# relay.net
KiCad netlist of a schematic drawn in Altium Designer
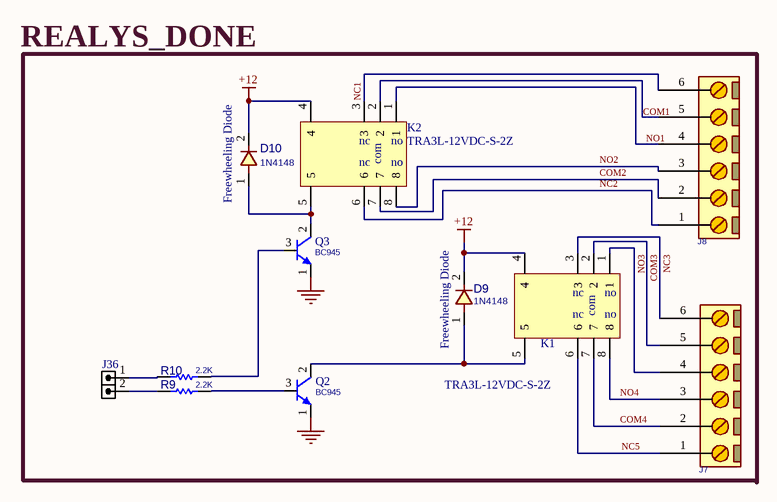
[diagram p0: relay.SchDoc]

(export (version "E")
  (design (tool "Eeschema 10.0.6"))
  (components
    (comp (ref "D9")
      (value "1N4148")
      (footprint "D_AX02_DO35")
      (description "DIODE, FAST SWTICHING, THD")
      (fields (field (name "MANF") "MANF"))
      (libsource (lib "diode") (part "DIODE_THD_1N4148_DO35"))
    )
    (comp (ref "D10")
      (value "1N4148")
      (footprint "D_AX02_DO35")
      (description "DIODE, FAST SWTICHING, THD")
      (fields (field (name "MANF") "MANF"))
      (libsource (lib "diode") (part "DIODE_THD_1N4148_DO35"))
    )
    (comp (ref "J7")
      (value "CONN_TB6")
      (footprint "TBG_6")
      (description "CONN, TERMINAL BLOCK, 5.08mm pitch")
      (libsource (lib "conn_power_terminalB") (part "CONN_TB6"))
    )
    (comp (ref "J8")
      (value "CONN_TB6")
      (footprint "TBG_6")
      (description "CONN, TERMINAL BLOCK, 5.08mm pitch")
      (libsource (lib "conn_power_terminalB") (part "CONN_TB6"))
    )
    (comp (ref "J36")
      (value "HDRM2")
      (footprint "HDR_M_1X2")
      (description "CONN, HEADER, Male, pitch: 2.54mm, 2POS")
      (libsource (lib "conn_header_2.54mm_st") (part "HDR_M_1X2"))
    )
    (comp (ref "K1")
      (value "TRA3L-12VDC-S-2Z")
      (footprint "TR3_RELAY_TIANBO")
      (fields (field (name "MANF") "TIANBO"))
      (libsource (lib "AvrDevelopmentBoard") (part "RELAY_TRA3"))
    )
    (comp (ref "K2")
      (value "TRA3L-12VDC-S-2Z")
      (footprint "TR3_RELAY_TIANBO")
      (fields (field (name "MANF") "TIANBO"))
      (libsource (lib "AvrDevelopmentBoard") (part "RELAY_TRA3"))
    )
    (comp (ref "Q2")
      (value "BC945")
      (footprint "TO92_3")
      (description "BJT, NPN, 50v, 0.15A, THD, TO92, BC945")
      (fields (field (name "MANF_P#") "2SC945, BC945"))
      (libsource (lib "transistor_bjt") (part "NPN_BC945_TO92"))
    )
    (comp (ref "Q3")
      (value "BC945")
      (footprint "TO92_3")
      (description "BJT, NPN, 50v, 0.15A, THD, TO92, BC945")
      (fields (field (name "MANF_P#") "2SC945, BC945"))
      (libsource (lib "transistor_bjt") (part "NPN_BC945_TO92"))
    )
    (comp (ref "R9")
      (value "2.2K")
      (footprint "R025W_AX04")
      (description "RESISTOR, THD")
      (fields (field (name "MANF_P#") "RK73H1ETTP4701F") (field (name "MANF") "KOA SPEER"))
      (libsource (lib "passive_thd") (part "RES_THD"))
    )
    (comp (ref "R10")
      (value "2.2K")
      (footprint "R025W_AX04")
      (description "RESISTOR, THD")
      (fields (field (name "MANF_P#") "RK73H1ETTP4701F") (field (name "MANF") "KOA SPEER"))
      (libsource (lib "passive_thd") (part "RES_THD"))
    )
  )
  (nets
    (net (code "1") (name "+12") (class "Default")
      (node (ref "D10") (pin "2") (pinfunction "2_2") (pintype "passive"))
      (node (ref "D9") (pin "2") (pinfunction "2_2") (pintype "passive"))
      (node (ref "K1") (pin "4") (pinfunction "4_4") (pintype "passive"))
      (node (ref "K2") (pin "4") (pinfunction "4_4") (pintype "passive"))
    )
    (net (code "3") (name "/COM2") (class "Default")
      (node (ref "J8") (pin "2") (pinfunction "2_2") (pintype "passive"))
      (node (ref "K2") (pin "7") (pinfunction "7_7") (pintype "passive"))
    )
    (net (code "4") (name "/COM3") (class "Default")
      (node (ref "J7") (pin "5") (pinfunction "5_5") (pintype "passive"))
      (node (ref "K1") (pin "2") (pinfunction "2_2") (pintype "passive"))
    )
    (net (code "6") (name "/COM4") (class "Default")
      (node (ref "J7") (pin "2") (pinfunction "2_2") (pintype "passive"))
      (node (ref "K1") (pin "7") (pinfunction "7_7") (pintype "passive"))
    )
    (net (code "7") (name "/NC1") (class "Default")
      (node (ref "J8") (pin "6") (pinfunction "6_6") (pintype "passive"))
      (node (ref "K2") (pin "3") (pinfunction "3_3") (pintype "passive"))
    )
    (net (code "8") (name "/NC2") (class "Default")
      (node (ref "J8") (pin "1") (pinfunction "1_1") (pintype "passive"))
      (node (ref "K2") (pin "6") (pinfunction "6_6") (pintype "passive"))
    )
    (net (code "9") (name "/NC3") (class "Default")
      (node (ref "J7") (pin "6") (pinfunction "6_6") (pintype "passive"))
      (node (ref "K1") (pin "3") (pinfunction "3_3") (pintype "passive"))
    )
    (net (code "11") (name "/NC5") (class "Default")
      (node (ref "J7") (pin "1") (pinfunction "1_1") (pintype "passive"))
      (node (ref "K1") (pin "6") (pinfunction "6_6") (pintype "passive"))
    )
    (net (code "12") (name "/NO2") (class "Default")
      (node (ref "J8") (pin "3") (pinfunction "3_3") (pintype "passive"))
      (node (ref "K2") (pin "8") (pinfunction "8_8") (pintype "passive"))
    )
    (net (code "14") (name "/NO3") (class "Default")
      (node (ref "J7") (pin "4") (pinfunction "4_4") (pintype "passive"))
      (node (ref "K1") (pin "1") (pinfunction "1_1") (pintype "passive"))
    )
    (net (code "15") (name "/NO4") (class "Default")
      (node (ref "J7") (pin "3") (pinfunction "3_3") (pintype "passive"))
      (node (ref "K1") (pin "8") (pinfunction "8_8") (pintype "passive"))
    )
    (net (code "16") (name "GND") (class "Default")
      (node (ref "Q2") (pin "1") (pinfunction "E_1") (pintype "passive"))
      (node (ref "Q3") (pin "1") (pinfunction "E_1") (pintype "passive"))
    )
    (net (code "17") (name "Net-(J8-Pad4)") (class "Default")
      (node (ref "J8") (pin "4") (pinfunction "4_4") (pintype "passive"))
      (node (ref "K2") (pin "1") (pinfunction "1_1") (pintype "passive"))
    )
    (net (code "18") (name "Net-(J8-Pad5)") (class "Default")
      (node (ref "J8") (pin "5") (pinfunction "5_5") (pintype "passive"))
      (node (ref "K2") (pin "2") (pinfunction "2_2") (pintype "passive"))
    )
    (net (code "19") (name "Net-(J36-Pad1)") (class "Default")
      (node (ref "J36") (pin "1") (pinfunction "1_1") (pintype "passive"))
      (node (ref "R10") (pin "1") (pinfunction "1_1") (pintype "passive"))
    )
    (net (code "20") (name "Net-(J36-Pad2)") (class "Default")
      (node (ref "J36") (pin "2") (pinfunction "2_2") (pintype "passive"))
      (node (ref "R9") (pin "1") (pinfunction "1_1") (pintype "passive"))
    )
    (net (code "21") (name "Net-(Q2-B)") (class "Default")
      (node (ref "Q2") (pin "3") (pinfunction "B_3") (pintype "passive"))
      (node (ref "R9") (pin "2") (pinfunction "2_2") (pintype "passive"))
    )
    (net (code "22") (name "Net-(Q2-C)") (class "Default")
      (node (ref "D9") (pin "1") (pinfunction "1_1") (pintype "passive"))
      (node (ref "K1") (pin "5") (pinfunction "5_5") (pintype "passive"))
      (node (ref "Q2") (pin "2") (pinfunction "C_2") (pintype "passive"))
    )
    (net (code "23") (name "Net-(Q3-B)") (class "Default")
      (node (ref "Q3") (pin "3") (pinfunction "B_3") (pintype "passive"))
      (node (ref "R10") (pin "2") (pinfunction "2_2") (pintype "passive"))
    )
    (net (code "24") (name "Net-(Q3-C)") (class "Default")
      (node (ref "D10") (pin "1") (pinfunction "1_1") (pintype "passive"))
      (node (ref "K2") (pin "5") (pinfunction "5_5") (pintype "passive"))
      (node (ref "Q3") (pin "2") (pinfunction "C_2") (pintype "passive"))
    )
  )
)
